# ground_station_boardv1_1.net
KiCad netlist of a schematic drawn in EAGLE
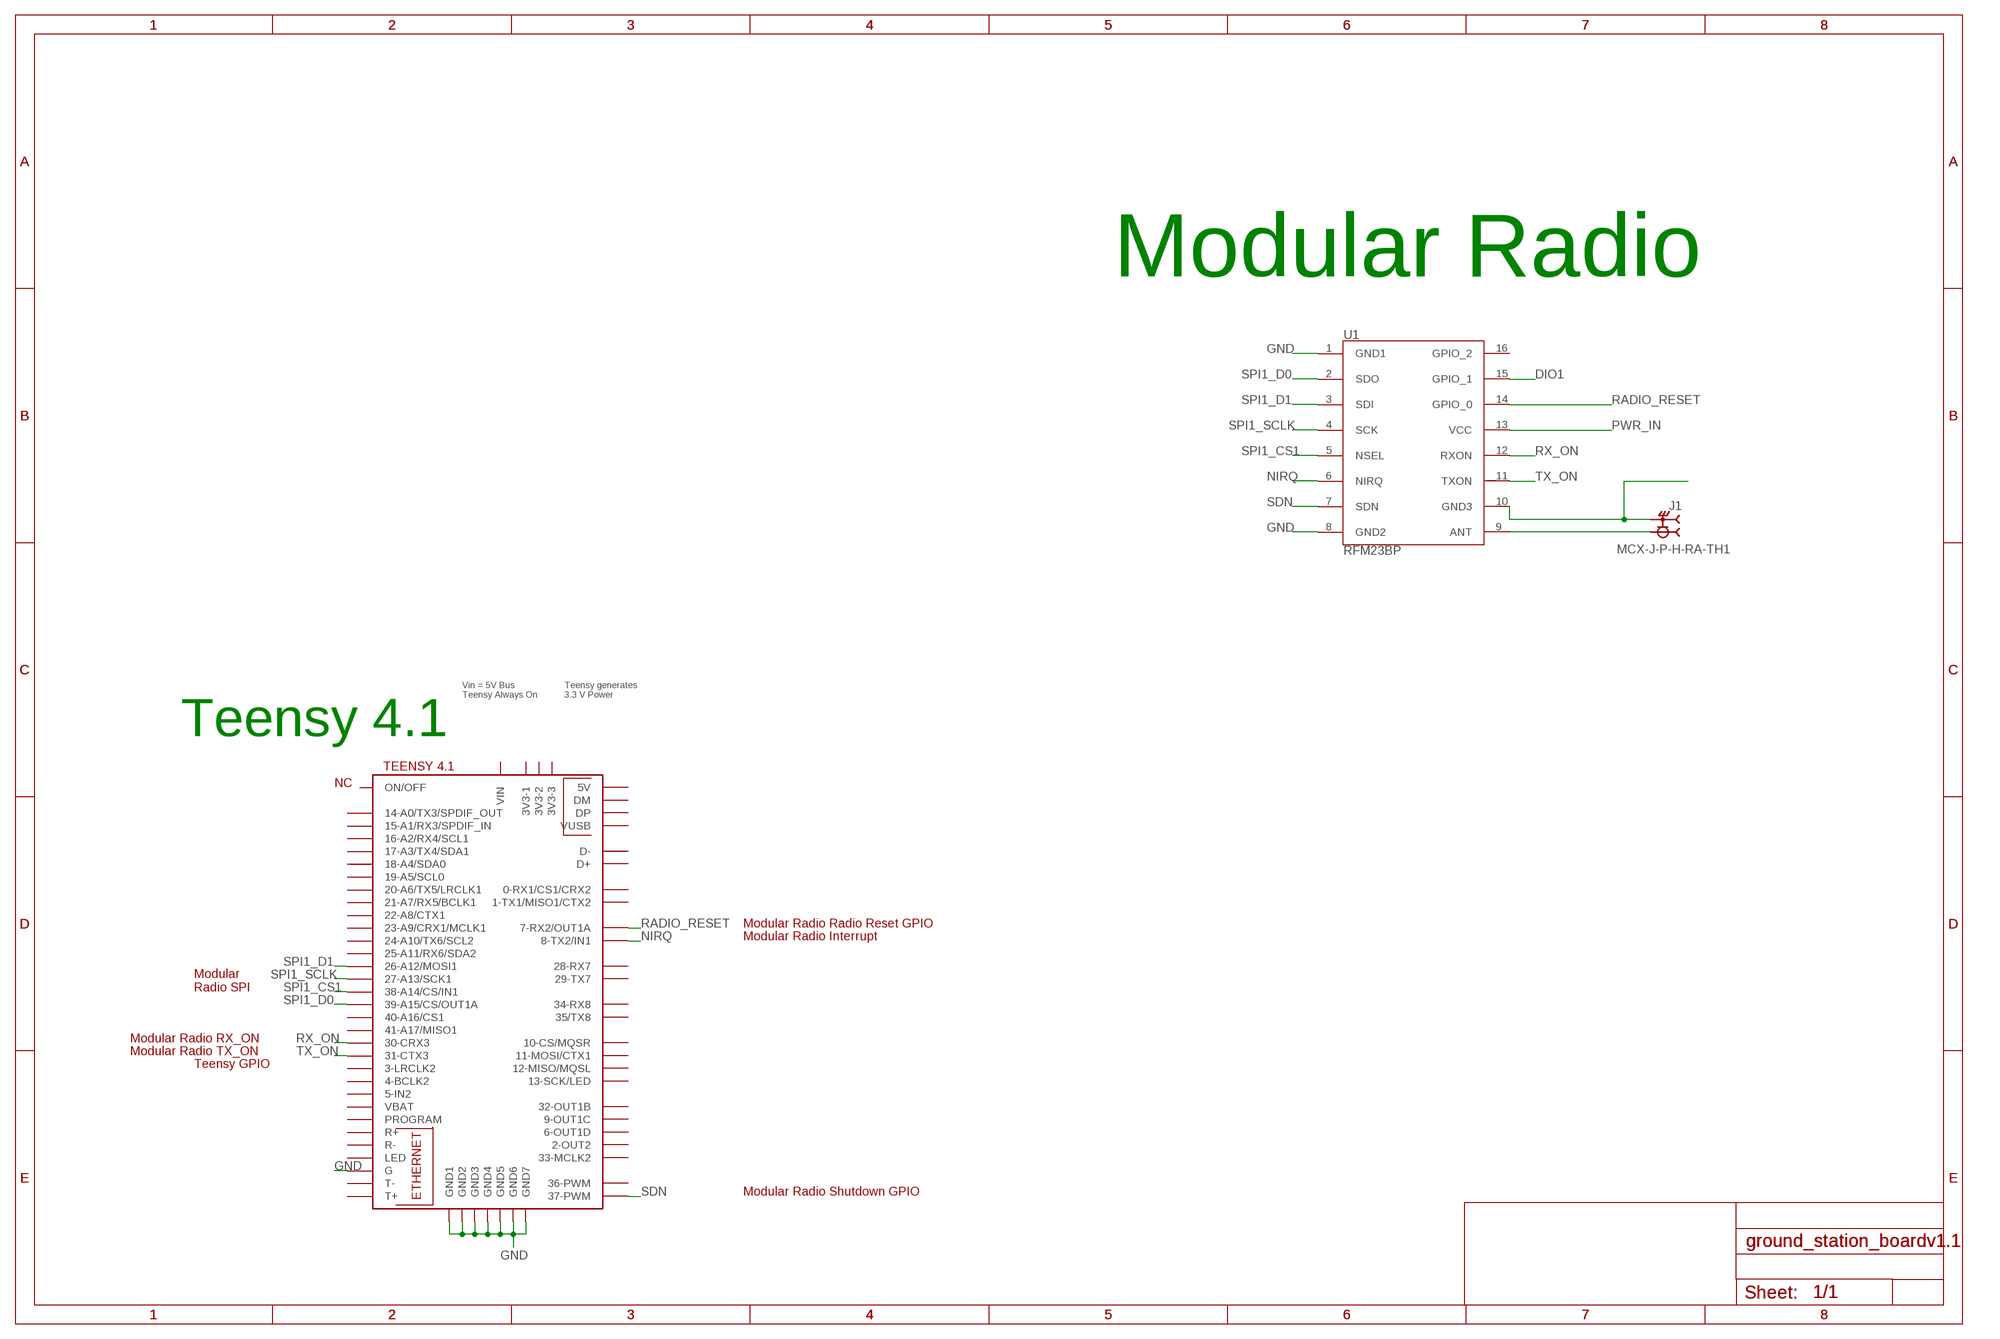
[diagram p0: schematic, sheet 1]

(export (version "E")
  (design (tool "Eeschema 10.0.6"))
  (components
    (comp (ref "J1")
      (value "MCX-J-P-H-RA-TH1")
      (footprint "eagle-import:SAMTEC_MCX-J-P-H-RA-TH1")
      (fields (field (name "DIGI-KEY_PART_NUMBER") "SAM10607-ND") (field (name "MF") "Samtec"))
      (libsource (lib "eagle-import") (part "MCX-J-P-H-RA-TH1"))
    )
    (comp (ref "U$1")
      (value "TEENSY41TEENSY")
      (footprint "eagle-import:TEENSY41")
      (libsource (lib "eagle-import") (part "TEENSY41TEENSY"))
    )
    (comp (ref "U1")
      (value "RFM23BP")
      (footprint "eagle-import:RFM23BP")
      (libsource (lib "eagle-import") (part "RFM23BP"))
    )
  )
  (nets
    (net (code "1") (name "/DIO1") (class "Default")
      (node (ref "U1") (pin "15") (pinfunction "GPIO_1_15") (pintype "bidirectional"))
    )
    (net (code "2") (name "/GND") (class "Default")
      (node (ref "U$1") (pin "G") (pinfunction "G_G") (pintype "bidirectional"))
      (node (ref "U$1") (pin "GND") (pinfunction "GND7_GND") (pintype "bidirectional"))
      (node (ref "U$1") (pin "GND1") (pinfunction "GND1_GND1") (pintype "bidirectional"))
      (node (ref "U$1") (pin "GND2") (pinfunction "GND2_GND2") (pintype "bidirectional"))
      (node (ref "U$1") (pin "GND3") (pinfunction "GND3_GND3") (pintype "bidirectional"))
      (node (ref "U$1") (pin "GND4") (pinfunction "GND4_GND4") (pintype "bidirectional"))
      (node (ref "U$1") (pin "GND5") (pinfunction "GND5_GND5") (pintype "bidirectional"))
      (node (ref "U$1") (pin "GND6") (pinfunction "GND6_GND6") (pintype "bidirectional"))
      (node (ref "U1") (pin "1") (pinfunction "GND1_1") (pintype "bidirectional"))
      (node (ref "U1") (pin "8") (pinfunction "GND2_8") (pintype "bidirectional"))
    )
    (net (code "3") (name "/NIRQ") (class "Default")
      (node (ref "U$1") (pin "8-TX2/IN1") (pinfunction "8-TX2/IN1_8-TX2/IN1") (pintype "bidirectional"))
      (node (ref "U1") (pin "6") (pinfunction "NIRQ_6") (pintype "bidirectional"))
    )
    (net (code "4") (name "/PWR_IN") (class "Default")
      (node (ref "U1") (pin "13") (pinfunction "VCC_13") (pintype "bidirectional"))
    )
    (net (code "5") (name "/RADIO_RESET") (class "Default")
      (node (ref "U$1") (pin "7-RX2/OUT1A") (pinfunction "7-RX2/OUT1A_7-RX2/OUT1A") (pintype "bidirectional"))
      (node (ref "U1") (pin "14") (pinfunction "GPIO_0_14") (pintype "bidirectional"))
    )
    (net (code "6") (name "/RX_ON") (class "Default")
      (node (ref "U$1") (pin "30-CRX3") (pinfunction "30-CRX3_30-CRX3") (pintype "bidirectional"))
      (node (ref "U1") (pin "12") (pinfunction "RXON_12") (pintype "bidirectional"))
    )
    (net (code "7") (name "/SDN") (class "Default")
      (node (ref "U$1") (pin "37-PWM") (pinfunction "37-PWM_37-PWM") (pintype "bidirectional"))
      (node (ref "U1") (pin "7") (pinfunction "SDN_7") (pintype "bidirectional"))
    )
    (net (code "8") (name "/SPI1_CS1") (class "Default")
      (node (ref "U$1") (pin "38-A14/CS/IN1") (pinfunction "38-A14/CS/IN1_38-A14/CS/IN1") (pintype "bidirectional"))
      (node (ref "U1") (pin "5") (pinfunction "NSEL_5") (pintype "bidirectional"))
    )
    (net (code "9") (name "/SPI1_D0") (class "Default")
      (node (ref "U$1") (pin "39-A15/CS/OUT1A") (pinfunction "39-A15/CS/OUT1A_39-A15/CS/OUT1A") (pintype "bidirectional"))
      (node (ref "U1") (pin "2") (pinfunction "SDO_2") (pintype "bidirectional"))
    )
    (net (code "10") (name "/SPI1_D1") (class "Default")
      (node (ref "U$1") (pin "26-A12/MOSI1") (pinfunction "26-A12/MOSI1_26-A12/MOSI1") (pintype "bidirectional"))
      (node (ref "U1") (pin "3") (pinfunction "SDI_3") (pintype "bidirectional"))
    )
    (net (code "11") (name "/SPI1_SCLK") (class "Default")
      (node (ref "U$1") (pin "27-A13/SCK1") (pinfunction "27-A13/SCK1_27-A13/SCK1") (pintype "bidirectional"))
      (node (ref "U1") (pin "4") (pinfunction "SCK_4") (pintype "bidirectional"))
    )
    (net (code "12") (name "/TX_ON") (class "Default")
      (node (ref "U$1") (pin "31-CTX3") (pinfunction "31-CTX3_31-CTX3") (pintype "bidirectional"))
      (node (ref "U1") (pin "11") (pinfunction "TXON_11") (pintype "bidirectional"))
    )
    (net (code "13") (name "Net-(U1-ANT)") (class "Default")
      (node (ref "J1") (pin "1") (pinfunction "1_1") (pintype "passive"))
      (node (ref "U1") (pin "9") (pinfunction "ANT_9") (pintype "bidirectional"))
    )
    (net (code "14") (name "Net-(U1-GND3)") (class "Default")
      (node (ref "J1") (pin "S1") (pinfunction "2_S1") (pintype "passive"))
      (node (ref "J1") (pin "S2") (pinfunction "2_S2") (pintype "passive"))
      (node (ref "J1") (pin "S3") (pinfunction "2_S3") (pintype "passive"))
      (node (ref "J1") (pin "S4") (pinfunction "2_S4") (pintype "passive"))
      (node (ref "U1") (pin "10") (pinfunction "GND3_10") (pintype "bidirectional"))
    )
    (net (code "15") (name "unconnected-(U$1-5V-Pad+5V)") (class "Default")
      (node (ref "U$1") (pin "+5V") (pinfunction "5V_+5V") (pintype "bidirectional"))
    )
    (net (code "16") (name "unconnected-(U$1-10-CS{slash}MQSR-Pad10-CS\\MQSR)") (class "Default")
      (node (ref "U$1") (pin "10-CS\\MQSR") (pinfunction "10-CS/MQSR_10-CS\\MQSR") (pintype "bidirectional"))
    )
    (net (code "17") (name "unconnected-(U$1-35{slash}TX8-Pad35-TX8)") (class "Default")
      (node (ref "U$1") (pin "35-TX8") (pinfunction "35/TX8_35-TX8") (pintype "bidirectional"))
    )
    (net (code "18") (name "unconnected-(U$1-Pad0-RX1{slash}CS1{slash}CRX2)") (class "Default")
      (node (ref "U$1") (pin "0-RX1/CS1/CRX2") (pinfunction "0-RX1/CS1/CRX2_0-RX1/CS1/CRX2") (pintype "bidirectional"))
    )
    (net (code "19") (name "unconnected-(U$1-Pad1-TX1{slash}MISO1{slash}CTX2)") (class "Default")
      (node (ref "U$1") (pin "1-TX1/MISO1/CTX2") (pinfunction "1-TX1/MISO1/CTX2_1-TX1/MISO1/CTX2") (pintype "bidirectional"))
    )
    (net (code "20") (name "unconnected-(U$1-Pad2-OUT2)") (class "Default")
      (node (ref "U$1") (pin "2-OUT2") (pinfunction "2-OUT2_2-OUT2") (pintype "bidirectional"))
    )
    (net (code "21") (name "unconnected-(U$1-Pad3-LRCLK2)") (class "Default")
      (node (ref "U$1") (pin "3-LRCLK2") (pinfunction "3-LRCLK2_3-LRCLK2") (pintype "bidirectional"))
    )
    (net (code "22") (name "unconnected-(U$1-Pad3V3-1)") (class "Default")
      (node (ref "U$1") (pin "3V3-1") (pinfunction "3V3-1_3V3-1") (pintype "bidirectional"))
    )
    (net (code "23") (name "unconnected-(U$1-Pad3V3-2)") (class "Default")
      (node (ref "U$1") (pin "3V3-2") (pinfunction "3V3-2_3V3-2") (pintype "bidirectional"))
    )
    (net (code "24") (name "unconnected-(U$1-Pad3V3-3)") (class "Default")
      (node (ref "U$1") (pin "3V3-3") (pinfunction "3V3-3_3V3-3") (pintype "bidirectional"))
    )
    (net (code "25") (name "unconnected-(U$1-Pad4-BCLK2)") (class "Default")
      (node (ref "U$1") (pin "4-BCLK2") (pinfunction "4-BCLK2_4-BCLK2") (pintype "bidirectional"))
    )
    (net (code "26") (name "unconnected-(U$1-Pad5-IN2)") (class "Default")
      (node (ref "U$1") (pin "5-IN2") (pinfunction "5-IN2_5-IN2") (pintype "bidirectional"))
    )
    (net (code "27") (name "unconnected-(U$1-Pad6-OUT1D)") (class "Default")
      (node (ref "U$1") (pin "6-OUT1D") (pinfunction "6-OUT1D_6-OUT1D") (pintype "bidirectional"))
    )
    (net (code "28") (name "unconnected-(U$1-Pad9-OUT1C)") (class "Default")
      (node (ref "U$1") (pin "9-OUT1C") (pinfunction "9-OUT1C_9-OUT1C") (pintype "bidirectional"))
    )
    (net (code "29") (name "unconnected-(U$1-Pad11-MOSI{slash}CTX1)") (class "Default")
      (node (ref "U$1") (pin "11-MOSI/CTX1") (pinfunction "11-MOSI/CTX1_11-MOSI/CTX1") (pintype "bidirectional"))
    )
    (net (code "30") (name "unconnected-(U$1-Pad12-MISO{slash}MQSL)") (class "Default")
      (node (ref "U$1") (pin "12-MISO/MQSL") (pinfunction "12-MISO/MQSL_12-MISO/MQSL") (pintype "bidirectional"))
    )
    (net (code "31") (name "unconnected-(U$1-Pad13-SCK{slash}LED)") (class "Default")
      (node (ref "U$1") (pin "13-SCK/LED") (pinfunction "13-SCK/LED_13-SCK/LED") (pintype "bidirectional"))
    )
    (net (code "32") (name "unconnected-(U$1-Pad14-A0{slash}TX3{slash}SPDIF_OUT)") (class "Default")
      (node (ref "U$1") (pin "14-A0/TX3/SPDIF_OUT") (pinfunction "14-A0/TX3/SPDIF_OUT_14-A0/TX3/SPDIF_OUT") (pintype "bidirectional"))
    )
    (net (code "33") (name "unconnected-(U$1-Pad15-A1{slash}RX3{slash}SPDIF_IN)") (class "Default")
      (node (ref "U$1") (pin "15-A1/RX3/SPDIF_IN") (pinfunction "15-A1/RX3/SPDIF_IN_15-A1/RX3/SPDIF_IN") (pintype "bidirectional"))
    )
    (net (code "34") (name "unconnected-(U$1-Pad16-A2{slash}RX4{slash}SCL1)") (class "Default")
      (node (ref "U$1") (pin "16-A2/RX4/SCL1") (pinfunction "16-A2/RX4/SCL1_16-A2/RX4/SCL1") (pintype "bidirectional"))
    )
    (net (code "35") (name "unconnected-(U$1-Pad17-A3{slash}TX4{slash}SDA1)") (class "Default")
      (node (ref "U$1") (pin "17-A3/TX4/SDA1") (pinfunction "17-A3/TX4/SDA1_17-A3/TX4/SDA1") (pintype "bidirectional"))
    )
    (net (code "36") (name "unconnected-(U$1-Pad18-A4{slash}SDA0)") (class "Default")
      (node (ref "U$1") (pin "18-A4/SDA0") (pinfunction "18-A4/SDA0_18-A4/SDA0") (pintype "bidirectional"))
    )
    (net (code "37") (name "unconnected-(U$1-Pad19-A5{slash}SCL0)") (class "Default")
      (node (ref "U$1") (pin "19-A5/SCL0") (pinfunction "19-A5/SCL0_19-A5/SCL0") (pintype "bidirectional"))
    )
    (net (code "38") (name "unconnected-(U$1-Pad20-A6{slash}TX5{slash}LRCLK1)") (class "Default")
      (node (ref "U$1") (pin "20-A6/TX5/LRCLK1") (pinfunction "20-A6/TX5/LRCLK1_20-A6/TX5/LRCLK1") (pintype "bidirectional"))
    )
    (net (code "39") (name "unconnected-(U$1-Pad21-A7{slash}RX5{slash}BCLK1)") (class "Default")
      (node (ref "U$1") (pin "21-A7/RX5/BCLK1") (pinfunction "21-A7/RX5/BCLK1_21-A7/RX5/BCLK1") (pintype "bidirectional"))
    )
    (net (code "40") (name "unconnected-(U$1-Pad22-A8{slash}CTX1)") (class "Default")
      (node (ref "U$1") (pin "22-A8/CTX1") (pinfunction "22-A8/CTX1_22-A8/CTX1") (pintype "bidirectional"))
    )
    (net (code "41") (name "unconnected-(U$1-Pad23-A9{slash}CRX1{slash}MCLK1)") (class "Default")
      (node (ref "U$1") (pin "23-A9/CRX1/MCLK1") (pinfunction "23-A9/CRX1/MCLK1_23-A9/CRX1/MCLK1") (pintype "bidirectional"))
    )
    (net (code "42") (name "unconnected-(U$1-Pad24-A10{slash}TX6{slash}SCL2)") (class "Default")
      (node (ref "U$1") (pin "24-A10/TX6/SCL2") (pinfunction "24-A10/TX6/SCL2_24-A10/TX6/SCL2") (pintype "bidirectional"))
    )
    (net (code "43") (name "unconnected-(U$1-Pad25-A11{slash}RX6{slash}SDA2)") (class "Default")
      (node (ref "U$1") (pin "25-A11/RX6/SDA2") (pinfunction "25-A11/RX6/SDA2_25-A11/RX6/SDA2") (pintype "bidirectional"))
    )
    (net (code "44") (name "unconnected-(U$1-Pad28-RX7)") (class "Default")
      (node (ref "U$1") (pin "28-RX7") (pinfunction "28-RX7_28-RX7") (pintype "bidirectional"))
    )
    (net (code "45") (name "unconnected-(U$1-Pad29-TX7)") (class "Default")
      (node (ref "U$1") (pin "29-TX7") (pinfunction "29-TX7_29-TX7") (pintype "bidirectional"))
    )
    (net (code "46") (name "unconnected-(U$1-Pad32-OUT1B)") (class "Default")
      (node (ref "U$1") (pin "32-OUT1B") (pinfunction "32-OUT1B_32-OUT1B") (pintype "bidirectional"))
    )
    (net (code "47") (name "unconnected-(U$1-Pad33-MCLK2)") (class "Default")
      (node (ref "U$1") (pin "33-MCLK2") (pinfunction "33-MCLK2_33-MCLK2") (pintype "bidirectional"))
    )
    (net (code "48") (name "unconnected-(U$1-Pad34-RX8)") (class "Default")
      (node (ref "U$1") (pin "34-RX8") (pinfunction "34-RX8_34-RX8") (pintype "bidirectional"))
    )
    (net (code "49") (name "unconnected-(U$1-Pad36-PWM)") (class "Default")
      (node (ref "U$1") (pin "36-PWM") (pinfunction "36-PWM_36-PWM") (pintype "bidirectional"))
    )
    (net (code "50") (name "unconnected-(U$1-Pad40-A16{slash}CS1)") (class "Default")
      (node (ref "U$1") (pin "40-A16/CS1") (pinfunction "40-A16/CS1_40-A16/CS1") (pintype "bidirectional"))
    )
    (net (code "51") (name "unconnected-(U$1-Pad41-A17{slash}MISO1)") (class "Default")
      (node (ref "U$1") (pin "41-A17/MISO1") (pinfunction "41-A17/MISO1_41-A17/MISO1") (pintype "bidirectional"))
    )
    (net (code "52") (name "unconnected-(U$1-PadD+)") (class "Default")
      (node (ref "U$1") (pin "D+") (pinfunction "D+_D+") (pintype "bidirectional"))
    )
    (net (code "53") (name "unconnected-(U$1-PadD-)") (class "Default")
      (node (ref "U$1") (pin "D-") (pinfunction "D-_D-") (pintype "bidirectional"))
    )
    (net (code "54") (name "unconnected-(U$1-PadDM)") (class "Default")
      (node (ref "U$1") (pin "DM") (pinfunction "DM_DM") (pintype "bidirectional"))
    )
    (net (code "55") (name "unconnected-(U$1-PadDP)") (class "Default")
      (node (ref "U$1") (pin "DP") (pinfunction "DP_DP") (pintype "bidirectional"))
    )
    (net (code "56") (name "unconnected-(U$1-PadLED)") (class "Default")
      (node (ref "U$1") (pin "LED") (pinfunction "LED_LED") (pintype "bidirectional"))
    )
    (net (code "57") (name "unconnected-(U$1-PadON{slash}OFF)") (class "Default")
      (node (ref "U$1") (pin "ON/OFF") (pinfunction "ON/OFF_ON/OFF") (pintype "bidirectional"))
    )
    (net (code "58") (name "unconnected-(U$1-PadPROGRAM)") (class "Default")
      (node (ref "U$1") (pin "PROGRAM") (pinfunction "PROGRAM_PROGRAM") (pintype "bidirectional"))
    )
    (net (code "59") (name "unconnected-(U$1-PadR+)") (class "Default")
      (node (ref "U$1") (pin "R+") (pinfunction "R+_R+") (pintype "bidirectional"))
    )
    (net (code "60") (name "unconnected-(U$1-PadR-)") (class "Default")
      (node (ref "U$1") (pin "R-") (pinfunction "R-_R-") (pintype "bidirectional"))
    )
    (net (code "61") (name "unconnected-(U$1-PadT+)") (class "Default")
      (node (ref "U$1") (pin "T+") (pinfunction "T+_T+") (pintype "bidirectional"))
    )
    (net (code "62") (name "unconnected-(U$1-PadT-)") (class "Default")
      (node (ref "U$1") (pin "T-") (pinfunction "T-_T-") (pintype "bidirectional"))
    )
    (net (code "63") (name "unconnected-(U$1-PadVBAT)") (class "Default")
      (node (ref "U$1") (pin "VBAT") (pinfunction "VBAT_VBAT") (pintype "bidirectional"))
    )
    (net (code "64") (name "unconnected-(U$1-PadVIN)") (class "Default")
      (node (ref "U$1") (pin "VIN") (pinfunction "VIN_VIN") (pintype "bidirectional"))
    )
    (net (code "65") (name "unconnected-(U$1-PadVUSB)") (class "Default")
      (node (ref "U$1") (pin "VUSB") (pinfunction "VUSB_VUSB") (pintype "bidirectional"))
    )
    (net (code "66") (name "unconnected-(U1-GPIO_2-Pad16)") (class "Default")
      (node (ref "U1") (pin "16") (pinfunction "GPIO_2_16") (pintype "bidirectional"))
    )
  )
)
